# AcceLog_v01.net
KiCad netlist of a schematic drawn in EAGLE
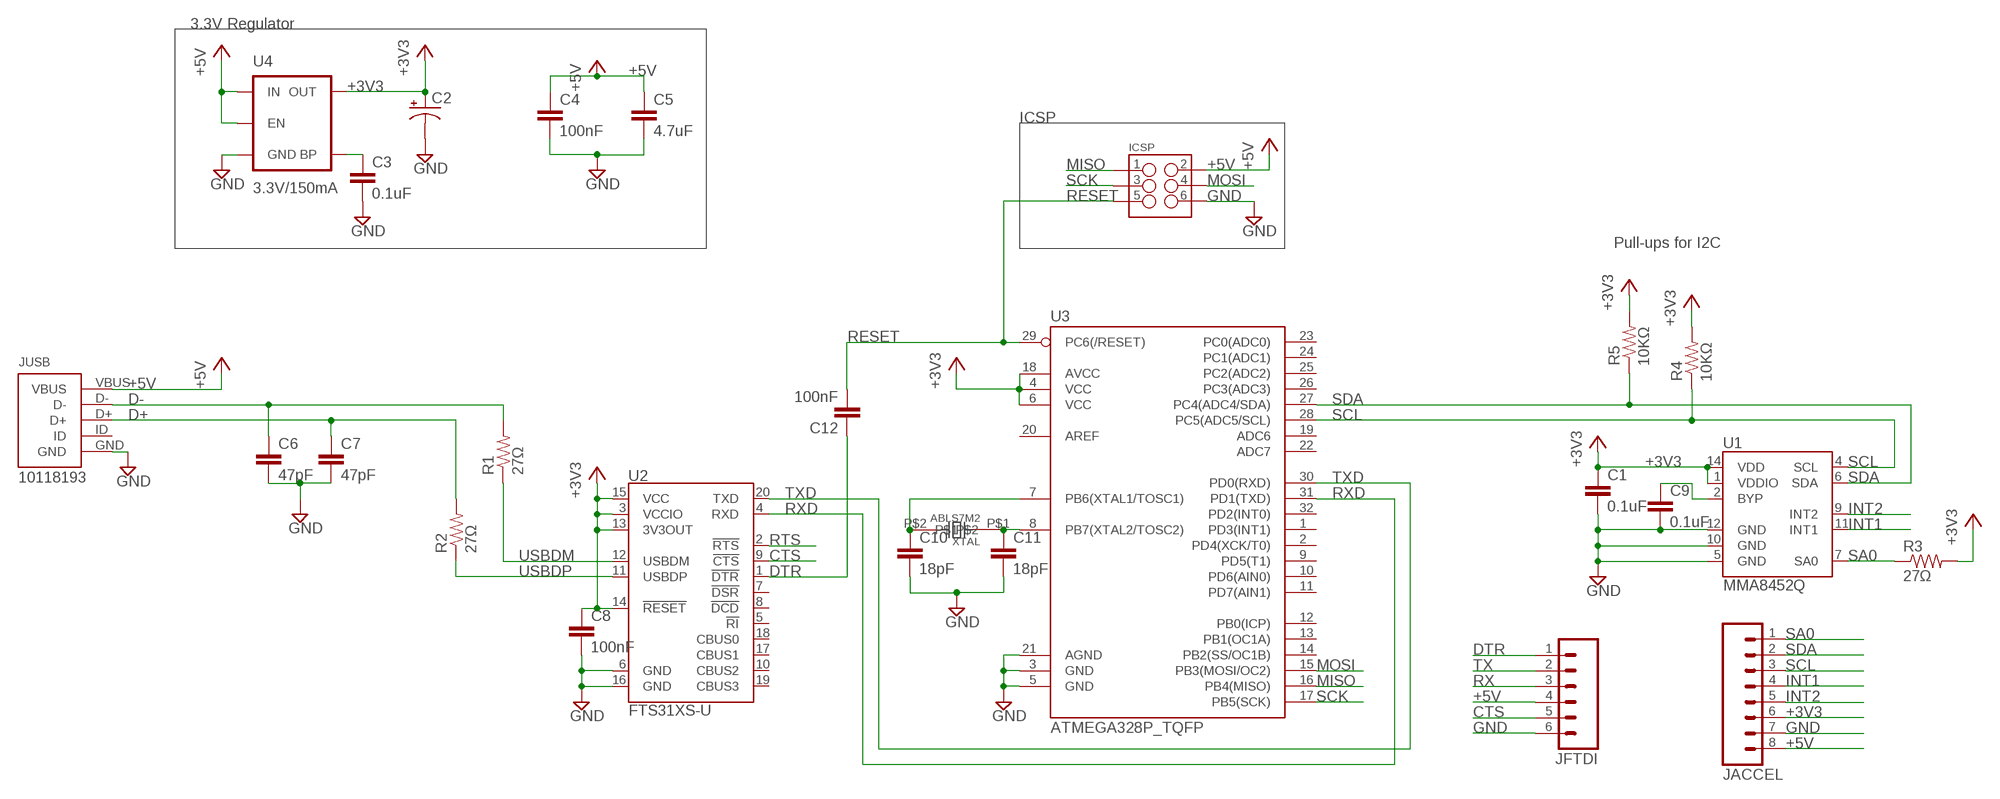
[diagram p0: schematic, sheet 1]

(export (version "E")
  (design (tool "Eeschema 10.0.6"))
  (components
    (comp (ref "C1")
      (value "0.1uF")
      (footprint "eagle-import:0603-CAP")
      (libsource (lib "eagle-import") (part "CAP0603-CAP"))
    )
    (comp (ref "C2")
      (value "CAP_POL1206")
      (footprint "eagle-import:EIA3216")
      (libsource (lib "eagle-import") (part "CAP_POL1206"))
    )
    (comp (ref "C3")
      (value "0.1uF")
      (footprint "eagle-import:0603-CAP")
      (libsource (lib "eagle-import") (part "CAP0603-CAP"))
    )
    (comp (ref "C4")
      (value "100nF")
      (footprint "eagle-import:0603-CAP")
      (libsource (lib "eagle-import") (part "CAP0603-CAP"))
    )
    (comp (ref "C5")
      (value "4.7uF")
      (footprint "eagle-import:0603-CAP")
      (libsource (lib "eagle-import") (part "CAP0603-CAP"))
    )
    (comp (ref "C6")
      (value "47pF")
      (footprint "eagle-import:0603-CAP")
      (libsource (lib "eagle-import") (part "CAP0603-CAP"))
    )
    (comp (ref "C7")
      (value "47pF")
      (footprint "eagle-import:0603-CAP")
      (libsource (lib "eagle-import") (part "CAP0603-CAP"))
    )
    (comp (ref "C8")
      (value "100nF")
      (footprint "eagle-import:0603-CAP")
      (libsource (lib "eagle-import") (part "CAP0603-CAP"))
    )
    (comp (ref "C9")
      (value "0.1uF")
      (footprint "eagle-import:0603-CAP")
      (libsource (lib "eagle-import") (part "CAP0603-CAP"))
    )
    (comp (ref "C10")
      (value "18pF")
      (footprint "eagle-import:0603-CAP")
      (libsource (lib "eagle-import") (part "CAP0603-CAP"))
    )
    (comp (ref "C11")
      (value "18pF")
      (footprint "eagle-import:0603-CAP")
      (libsource (lib "eagle-import") (part "CAP0603-CAP"))
    )
    (comp (ref "C12")
      (value "100nF")
      (footprint "eagle-import:0603-CAP")
      (libsource (lib "eagle-import") (part "CAP0603-CAP"))
    )
    (comp (ref "ICSP")
      (value "M03X22X3_SILK_MALE_PTH")
      (footprint "eagle-import:2X3")
      (libsource (lib "eagle-import") (part "M03X22X3_SILK_MALE_PTH"))
    )
    (comp (ref "JACCEL")
      (value "M08LOCK")
      (footprint "eagle-import:1X08_LOCK")
      (libsource (lib "eagle-import") (part "M08LOCK"))
    )
    (comp (ref "JFTDI")
      (value "M06LOCK")
      (footprint "eagle-import:1X06_LOCK")
      (libsource (lib "eagle-import") (part "M06LOCK"))
    )
    (comp (ref "JUSB")
      (value "10118193")
      (footprint "eagle-import:10118193")
      (libsource (lib "eagle-import") (part "10118193"))
    )
    (comp (ref "R1")
      (value "27Ω")
      (footprint "eagle-import:0603-RES")
      (libsource (lib "eagle-import") (part "RESISTOR0603-RES"))
    )
    (comp (ref "R2")
      (value "27Ω")
      (footprint "eagle-import:0603-RES")
      (libsource (lib "eagle-import") (part "RESISTOR0603-RES"))
    )
    (comp (ref "R3")
      (value "27Ω")
      (footprint "eagle-import:0603-RES")
      (libsource (lib "eagle-import") (part "RESISTOR0603-RES"))
    )
    (comp (ref "R4")
      (value "10KΩ")
      (footprint "eagle-import:0603-RES")
      (libsource (lib "eagle-import") (part "RESISTOR0603-RES"))
    )
    (comp (ref "R5")
      (value "10KΩ")
      (footprint "eagle-import:0603-RES")
      (libsource (lib "eagle-import") (part "RESISTOR0603-RES"))
    )
    (comp (ref "U1")
      (value "MMA8452Q")
      (footprint "eagle-import:QFN-16_0.5MM")
      (libsource (lib "eagle-import") (part "MMA8452Q"))
    )
    (comp (ref "U2")
      (value "FTS31XS-U")
      (footprint "eagle-import:SSOP20_L")
      (libsource (lib "eagle-import") (part "FT231XS"))
    )
    (comp (ref "U3")
      (value "ATMEGA328P_TQFP")
      (footprint "eagle-import:TQFP32-08")
      (libsource (lib "eagle-import") (part "ATMEGA328P_TQFP"))
    )
    (comp (ref "U4")
      (value "3.3V/150mA")
      (footprint "eagle-import:SOT23-5")
      (libsource (lib "eagle-import") (part "V_REG_MIC52053.3V"))
    )
    (comp (ref "XTAL")
      (value "ABLS7M2")
      (footprint "eagle-import:ABLS7M2")
      (libsource (lib "eagle-import") (part "ABLS7M2"))
    )
  )
  (nets
    (net (code "1") (name "+3V3") (class "Default")
      (node (ref "C1") (pin "1") (pinfunction "1_1") (pintype "passive"))
      (node (ref "C2") (pin "A") (pinfunction "+_A") (pintype "passive"))
      (node (ref "C8") (pin "1") (pinfunction "1_1") (pintype "passive"))
      (node (ref "JACCEL") (pin "6") (pinfunction "6_6") (pintype "passive"))
      (node (ref "R3") (pin "2") (pinfunction "2_2") (pintype "passive"))
      (node (ref "R4") (pin "2") (pinfunction "2_2") (pintype "passive"))
      (node (ref "R5") (pin "2") (pinfunction "2_2") (pintype "passive"))
      (node (ref "U1") (pin "1") (pinfunction "VDDIO_1") (pintype "bidirectional"))
      (node (ref "U1") (pin "14") (pinfunction "VDD_14") (pintype "bidirectional"))
      (node (ref "U2") (pin "13") (pinfunction "3V3OUT_13") (pintype "bidirectional"))
      (node (ref "U2") (pin "14") (pinfunction "~{RESET}_14") (pintype "bidirectional"))
      (node (ref "U2") (pin "15") (pinfunction "VCC_15") (pintype "bidirectional"))
      (node (ref "U2") (pin "3") (pinfunction "VCCIO_3") (pintype "bidirectional"))
      (node (ref "U3") (pin "18") (pinfunction "AVCC_18") (pintype "bidirectional"))
      (node (ref "U3") (pin "4") (pinfunction "VCC_4") (pintype "bidirectional"))
      (node (ref "U3") (pin "6") (pinfunction "VCC_6") (pintype "bidirectional"))
      (node (ref "U4") (pin "5") (pinfunction "OUT_5") (pintype "passive"))
    )
    (net (code "2") (name "+5V") (class "Default")
      (node (ref "C4") (pin "1") (pinfunction "1_1") (pintype "passive"))
      (node (ref "C5") (pin "1") (pinfunction "1_1") (pintype "passive"))
      (node (ref "ICSP") (pin "2") (pinfunction "2_2") (pintype "bidirectional"))
      (node (ref "JACCEL") (pin "8") (pinfunction "8_8") (pintype "passive"))
      (node (ref "JFTDI") (pin "4") (pinfunction "4_4") (pintype "passive"))
      (node (ref "JUSB") (pin "VBUS") (pinfunction "VBUS_VBUS") (pintype "bidirectional"))
      (node (ref "U4") (pin "1") (pinfunction "IN_1") (pintype "input"))
      (node (ref "U4") (pin "3") (pinfunction "EN_3") (pintype "input"))
    )
    (net (code "3") (name "/CTS") (class "Default")
      (node (ref "JFTDI") (pin "5") (pinfunction "5_5") (pintype "passive"))
      (node (ref "U2") (pin "9") (pinfunction "~{CTS}_9") (pintype "bidirectional"))
    )
    (net (code "4") (name "/D+") (class "Default")
      (node (ref "C7") (pin "1") (pinfunction "1_1") (pintype "passive"))
      (node (ref "JUSB") (pin "D+") (pinfunction "D+_D+") (pintype "bidirectional"))
      (node (ref "R2") (pin "2") (pinfunction "2_2") (pintype "passive"))
    )
    (net (code "5") (name "/D-") (class "Default")
      (node (ref "C6") (pin "1") (pinfunction "1_1") (pintype "passive"))
      (node (ref "JUSB") (pin "D-") (pinfunction "D-_D-") (pintype "bidirectional"))
      (node (ref "R1") (pin "2") (pinfunction "2_2") (pintype "passive"))
    )
    (net (code "6") (name "/DTR") (class "Default")
      (node (ref "C12") (pin "1") (pinfunction "1_1") (pintype "passive"))
      (node (ref "JFTDI") (pin "1") (pinfunction "1_1") (pintype "passive"))
      (node (ref "U2") (pin "1") (pinfunction "~{DTR}_1") (pintype "bidirectional"))
    )
    (net (code "7") (name "/INT1") (class "Default")
      (node (ref "JACCEL") (pin "4") (pinfunction "4_4") (pintype "passive"))
      (node (ref "U1") (pin "11") (pinfunction "INT1_11") (pintype "bidirectional"))
    )
    (net (code "8") (name "/INT2") (class "Default")
      (node (ref "JACCEL") (pin "5") (pinfunction "5_5") (pintype "passive"))
      (node (ref "U1") (pin "9") (pinfunction "INT2_9") (pintype "bidirectional"))
    )
    (net (code "9") (name "/MISO") (class "Default")
      (node (ref "ICSP") (pin "1") (pinfunction "1_1") (pintype "bidirectional"))
      (node (ref "U3") (pin "16") (pinfunction "PB4(MISO)_16") (pintype "bidirectional"))
    )
    (net (code "10") (name "/MOSI") (class "Default")
      (node (ref "ICSP") (pin "4") (pinfunction "4_4") (pintype "bidirectional"))
      (node (ref "U3") (pin "15") (pinfunction "PB3(MOSI/OC2)_15") (pintype "bidirectional"))
    )
    (net (code "11") (name "/RESET") (class "Default")
      (node (ref "C12") (pin "2") (pinfunction "2_2") (pintype "passive"))
      (node (ref "ICSP") (pin "5") (pinfunction "5_5") (pintype "bidirectional"))
      (node (ref "U3") (pin "29") (pinfunction "PC6(/RESET)_29") (pintype "bidirectional"))
    )
    (net (code "12") (name "/RTS") (class "Default")
      (node (ref "U2") (pin "2") (pinfunction "~{RTS}_2") (pintype "bidirectional"))
    )
    (net (code "13") (name "/RX") (class "Default")
      (node (ref "JFTDI") (pin "3") (pinfunction "3_3") (pintype "passive"))
    )
    (net (code "14") (name "/RXD") (class "Default")
      (node (ref "U2") (pin "4") (pinfunction "RXD_4") (pintype "bidirectional"))
      (node (ref "U3") (pin "31") (pinfunction "PD1(TXD)_31") (pintype "bidirectional"))
    )
    (net (code "15") (name "/SA0") (class "Default")
      (node (ref "JACCEL") (pin "1") (pinfunction "1_1") (pintype "passive"))
      (node (ref "R3") (pin "1") (pinfunction "1_1") (pintype "passive"))
      (node (ref "U1") (pin "7") (pinfunction "SA0_7") (pintype "bidirectional"))
    )
    (net (code "16") (name "/SCK") (class "Default")
      (node (ref "ICSP") (pin "3") (pinfunction "3_3") (pintype "bidirectional"))
      (node (ref "U3") (pin "17") (pinfunction "PB5(SCK)_17") (pintype "bidirectional"))
    )
    (net (code "17") (name "/SCL") (class "Default")
      (node (ref "JACCEL") (pin "3") (pinfunction "3_3") (pintype "passive"))
      (node (ref "R4") (pin "1") (pinfunction "1_1") (pintype "passive"))
      (node (ref "U1") (pin "4") (pinfunction "SCL_4") (pintype "bidirectional"))
      (node (ref "U3") (pin "28") (pinfunction "PC5(ADC5/SCL)_28") (pintype "bidirectional"))
    )
    (net (code "18") (name "/SDA") (class "Default")
      (node (ref "JACCEL") (pin "2") (pinfunction "2_2") (pintype "passive"))
      (node (ref "R5") (pin "1") (pinfunction "1_1") (pintype "passive"))
      (node (ref "U1") (pin "6") (pinfunction "SDA_6") (pintype "bidirectional"))
      (node (ref "U3") (pin "27") (pinfunction "PC4(ADC4/SDA)_27") (pintype "bidirectional"))
    )
    (net (code "19") (name "/TX") (class "Default")
      (node (ref "JFTDI") (pin "2") (pinfunction "2_2") (pintype "passive"))
    )
    (net (code "20") (name "/TXD") (class "Default")
      (node (ref "U2") (pin "20") (pinfunction "TXD_20") (pintype "bidirectional"))
      (node (ref "U3") (pin "30") (pinfunction "PD0(RXD)_30") (pintype "bidirectional"))
    )
    (net (code "21") (name "/USBDM") (class "Default")
      (node (ref "R1") (pin "1") (pinfunction "1_1") (pintype "passive"))
      (node (ref "U2") (pin "12") (pinfunction "USBDM_12") (pintype "bidirectional"))
    )
    (net (code "22") (name "/USBDP") (class "Default")
      (node (ref "R2") (pin "1") (pinfunction "1_1") (pintype "passive"))
      (node (ref "U2") (pin "11") (pinfunction "USBDP_11") (pintype "bidirectional"))
    )
    (net (code "23") (name "GND") (class "Default")
      (node (ref "C1") (pin "2") (pinfunction "2_2") (pintype "passive"))
      (node (ref "C10") (pin "2") (pinfunction "2_2") (pintype "passive"))
      (node (ref "C11") (pin "2") (pinfunction "2_2") (pintype "passive"))
      (node (ref "C2") (pin "C") (pinfunction "-_C") (pintype "passive"))
      (node (ref "C3") (pin "2") (pinfunction "2_2") (pintype "passive"))
      (node (ref "C4") (pin "2") (pinfunction "2_2") (pintype "passive"))
      (node (ref "C5") (pin "2") (pinfunction "2_2") (pintype "passive"))
      (node (ref "C6") (pin "2") (pinfunction "2_2") (pintype "passive"))
      (node (ref "C7") (pin "2") (pinfunction "2_2") (pintype "passive"))
      (node (ref "C8") (pin "2") (pinfunction "2_2") (pintype "passive"))
      (node (ref "C9") (pin "2") (pinfunction "2_2") (pintype "passive"))
      (node (ref "ICSP") (pin "6") (pinfunction "6_6") (pintype "bidirectional"))
      (node (ref "JACCEL") (pin "7") (pinfunction "7_7") (pintype "passive"))
      (node (ref "JFTDI") (pin "6") (pinfunction "6_6") (pintype "passive"))
      (node (ref "JUSB") (pin "GND") (pinfunction "GND_GND") (pintype "bidirectional"))
      (node (ref "U1") (pin "10") (pinfunction "GND_10") (pintype "bidirectional"))
      (node (ref "U1") (pin "12") (pinfunction "GND_12") (pintype "bidirectional"))
      (node (ref "U1") (pin "5") (pinfunction "GND_5") (pintype "bidirectional"))
      (node (ref "U2") (pin "16") (pinfunction "GND_16") (pintype "bidirectional"))
      (node (ref "U2") (pin "6") (pinfunction "GND_6") (pintype "bidirectional"))
      (node (ref "U3") (pin "21") (pinfunction "AGND_21") (pintype "bidirectional"))
      (node (ref "U3") (pin "3") (pinfunction "GND_3") (pintype "bidirectional"))
      (node (ref "U3") (pin "5") (pinfunction "GND_5") (pintype "bidirectional"))
      (node (ref "U4") (pin "2") (pinfunction "GND_2") (pintype "input"))
    )
    (net (code "24") (name "Net-(U1-BYP)") (class "Default")
      (node (ref "C9") (pin "1") (pinfunction "1_1") (pintype "passive"))
      (node (ref "U1") (pin "2") (pinfunction "BYP_2") (pintype "bidirectional"))
    )
    (net (code "25") (name "Net-(U3-PB6(XTAL1{slash}TOSC1))") (class "Default")
      (node (ref "C10") (pin "1") (pinfunction "1_1") (pintype "passive"))
      (node (ref "U3") (pin "7") (pinfunction "PB6(XTAL1/TOSC1)_7") (pintype "bidirectional"))
      (node (ref "XTAL") (pin "P$2") (pinfunction "P$2_P$2") (pintype "bidirectional"))
    )
    (net (code "26") (name "Net-(U3-PB7(XTAL2{slash}TOSC2))") (class "Default")
      (node (ref "C11") (pin "1") (pinfunction "1_1") (pintype "passive"))
      (node (ref "U3") (pin "8") (pinfunction "PB7(XTAL2/TOSC2)_8") (pintype "bidirectional"))
      (node (ref "XTAL") (pin "P$1") (pinfunction "P$1_P$1") (pintype "bidirectional"))
    )
    (net (code "27") (name "Net-(U4-BP)") (class "Default")
      (node (ref "C3") (pin "1") (pinfunction "1_1") (pintype "passive"))
      (node (ref "U4") (pin "4") (pinfunction "BP_4") (pintype "input"))
    )
    (net (code "28") (name "unconnected-(JUSB-PadID)") (class "Default")
      (node (ref "JUSB") (pin "ID") (pinfunction "ID_ID") (pintype "bidirectional"))
    )
    (net (code "29") (name "unconnected-(U2-CBUS0-Pad18)") (class "Default")
      (node (ref "U2") (pin "18") (pinfunction "CBUS0_18") (pintype "bidirectional"))
    )
    (net (code "30") (name "unconnected-(U2-CBUS1-Pad17)") (class "Default")
      (node (ref "U2") (pin "17") (pinfunction "CBUS1_17") (pintype "bidirectional"))
    )
    (net (code "31") (name "unconnected-(U2-CBUS2-Pad10)") (class "Default")
      (node (ref "U2") (pin "10") (pinfunction "CBUS2_10") (pintype "bidirectional"))
    )
    (net (code "32") (name "unconnected-(U2-CBUS3-Pad19)") (class "Default")
      (node (ref "U2") (pin "19") (pinfunction "CBUS3_19") (pintype "bidirectional"))
    )
    (net (code "33") (name "unconnected-(U2-~{DCD}-Pad8)") (class "Default")
      (node (ref "U2") (pin "8") (pinfunction "~{DCD}_8") (pintype "bidirectional"))
    )
    (net (code "34") (name "unconnected-(U2-~{DSR}-Pad7)") (class "Default")
      (node (ref "U2") (pin "7") (pinfunction "~{DSR}_7") (pintype "bidirectional"))
    )
    (net (code "35") (name "unconnected-(U2-~{RI}-Pad5)") (class "Default")
      (node (ref "U2") (pin "5") (pinfunction "~{RI}_5") (pintype "bidirectional"))
    )
    (net (code "36") (name "unconnected-(U3-ADC6-Pad19)") (class "Default")
      (node (ref "U3") (pin "19") (pinfunction "ADC6_19") (pintype "bidirectional"))
    )
    (net (code "37") (name "unconnected-(U3-ADC7-Pad22)") (class "Default")
      (node (ref "U3") (pin "22") (pinfunction "ADC7_22") (pintype "bidirectional"))
    )
    (net (code "38") (name "unconnected-(U3-AREF-Pad20)") (class "Default")
      (node (ref "U3") (pin "20") (pinfunction "AREF_20") (pintype "bidirectional"))
    )
    (net (code "39") (name "unconnected-(U3-PB0(ICP)-Pad12)") (class "Default")
      (node (ref "U3") (pin "12") (pinfunction "PB0(ICP)_12") (pintype "bidirectional"))
    )
    (net (code "40") (name "unconnected-(U3-PB1(OC1A)-Pad13)") (class "Default")
      (node (ref "U3") (pin "13") (pinfunction "PB1(OC1A)_13") (pintype "bidirectional"))
    )
    (net (code "41") (name "unconnected-(U3-PB2(SS{slash}OC1B)-Pad14)") (class "Default")
      (node (ref "U3") (pin "14") (pinfunction "PB2(SS/OC1B)_14") (pintype "bidirectional"))
    )
    (net (code "42") (name "unconnected-(U3-PC0(ADC0)-Pad23)") (class "Default")
      (node (ref "U3") (pin "23") (pinfunction "PC0(ADC0)_23") (pintype "bidirectional"))
    )
    (net (code "43") (name "unconnected-(U3-PC1(ADC1)-Pad24)") (class "Default")
      (node (ref "U3") (pin "24") (pinfunction "PC1(ADC1)_24") (pintype "bidirectional"))
    )
    (net (code "44") (name "unconnected-(U3-PC2(ADC2)-Pad25)") (class "Default")
      (node (ref "U3") (pin "25") (pinfunction "PC2(ADC2)_25") (pintype "bidirectional"))
    )
    (net (code "45") (name "unconnected-(U3-PC3(ADC3)-Pad26)") (class "Default")
      (node (ref "U3") (pin "26") (pinfunction "PC3(ADC3)_26") (pintype "bidirectional"))
    )
    (net (code "46") (name "unconnected-(U3-PD2(INT0)-Pad32)") (class "Default")
      (node (ref "U3") (pin "32") (pinfunction "PD2(INT0)_32") (pintype "bidirectional"))
    )
    (net (code "47") (name "unconnected-(U3-PD3(INT1)-Pad1)") (class "Default")
      (node (ref "U3") (pin "1") (pinfunction "PD3(INT1)_1") (pintype "bidirectional"))
    )
    (net (code "48") (name "unconnected-(U3-PD4(XCK{slash}T0)-Pad2)") (class "Default")
      (node (ref "U3") (pin "2") (pinfunction "PD4(XCK/T0)_2") (pintype "bidirectional"))
    )
    (net (code "49") (name "unconnected-(U3-PD5(T1)-Pad9)") (class "Default")
      (node (ref "U3") (pin "9") (pinfunction "PD5(T1)_9") (pintype "bidirectional"))
    )
    (net (code "50") (name "unconnected-(U3-PD6(AIN0)-Pad10)") (class "Default")
      (node (ref "U3") (pin "10") (pinfunction "PD6(AIN0)_10") (pintype "bidirectional"))
    )
    (net (code "51") (name "unconnected-(U3-PD7(AIN1)-Pad11)") (class "Default")
      (node (ref "U3") (pin "11") (pinfunction "PD7(AIN1)_11") (pintype "bidirectional"))
    )
  )
)
